# Peripherals.net
KiCad netlist of a schematic drawn in Altium Designer
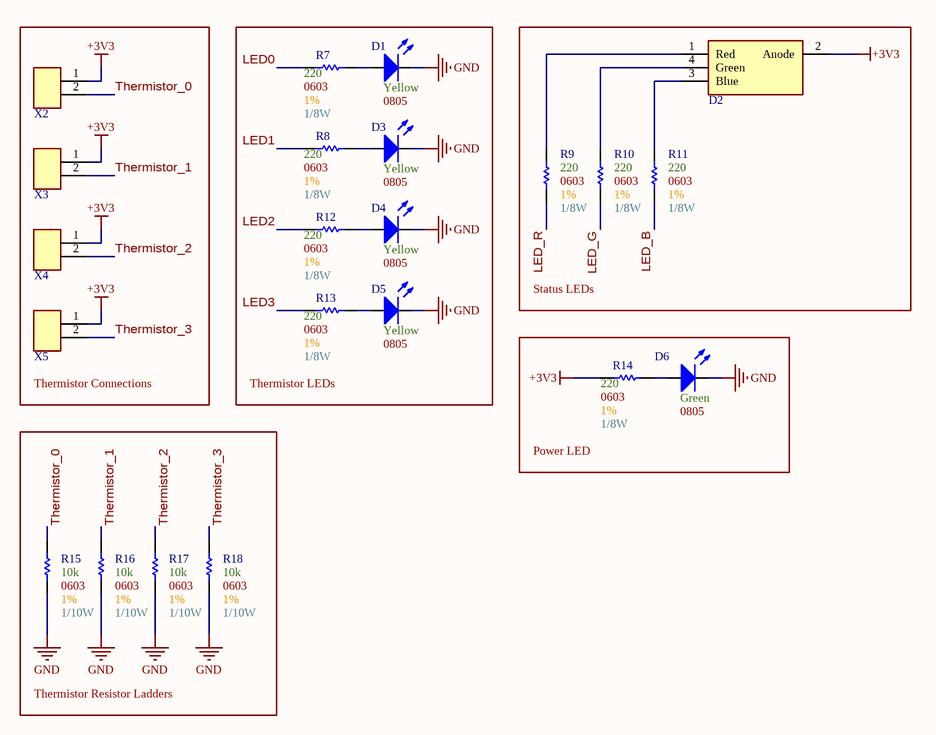
[diagram p0: Peripherals.SchDoc]

(export (version "E")
  (design (tool "Eeschema 10.0.6"))
  (components
    (comp (ref "D1")
      (value "[LED] SMD 0805 Yellow")
      (footprint "[LED] SMD 0805")
      (description "LY R976-PS-36-0-20-R18")
      (fields (field (name "COLOR") "Yellow") (field (name "SIZE PACKAGE") "0805"))
      (libsource (lib "LEDs") (part "[LED] SMD 0805 Yellow"))
    )
    (comp (ref "D2")
      (value "[LED] SMD RGB 1.55x1.55mm")
      (footprint "[LED] SMD RGB 1.55x1.55mm")
      (description "LTST-E143EGBW-P1")
      (libsource (lib "LEDs") (part "[LED] SMD RGB 1.55x1.55mm"))
    )
    (comp (ref "D3")
      (value "[LED] SMD 0805 Yellow")
      (footprint "[LED] SMD 0805")
      (description "LY R976-PS-36-0-20-R18")
      (fields (field (name "COLOR") "Yellow") (field (name "SIZE PACKAGE") "0805"))
      (libsource (lib "LEDs") (part "[LED] SMD 0805 Yellow"))
    )
    (comp (ref "D4")
      (value "[LED] SMD 0805 Yellow")
      (footprint "[LED] SMD 0805")
      (description "LY R976-PS-36-0-20-R18")
      (fields (field (name "COLOR") "Yellow") (field (name "SIZE PACKAGE") "0805"))
      (libsource (lib "LEDs") (part "[LED] SMD 0805 Yellow"))
    )
    (comp (ref "D5")
      (value "[LED] SMD 0805 Yellow")
      (footprint "[LED] SMD 0805")
      (description "LY R976-PS-36-0-20-R18")
      (fields (field (name "COLOR") "Yellow") (field (name "SIZE PACKAGE") "0805"))
      (libsource (lib "LEDs") (part "[LED] SMD 0805 Yellow"))
    )
    (comp (ref "D6")
      (value "[LED] SMD 0805 Green")
      (footprint "[LED] SMD 0805")
      (description "LG R971-KN-1-0-20-R18")
      (fields (field (name "COLOR") "Green") (field (name "SIZE PACKAGE") "0805"))
      (libsource (lib "LEDs") (part "[LED] SMD 0805 Green"))
    )
    (comp (ref "R7")
      (value "[220] SMD 0603 1% 1/10W")
      (footprint "[Res] SMD 0603")
      (description "CRGCQ0805F220R")
      (fields
        (field (name "WATTAGE") "1/8W")
        (field (name "TOLERANCE") "1%")
        (field (name "RESISTANCE") "220")
        (field (name "SIZE PACKAGE") "0603")
      )
      (libsource (lib "Resistors") (part "[220] SMD 0603 1% 1/10W"))
    )
    (comp (ref "R8")
      (value "[220] SMD 0603 1% 1/10W")
      (footprint "[Res] SMD 0603")
      (description "CRGCQ0805F220R")
      (fields
        (field (name "WATTAGE") "1/8W")
        (field (name "TOLERANCE") "1%")
        (field (name "RESISTANCE") "220")
        (field (name "SIZE PACKAGE") "0603")
      )
      (libsource (lib "Resistors") (part "[220] SMD 0603 1% 1/10W"))
    )
    (comp (ref "R9")
      (value "[220] SMD 0603 1% 1/10W")
      (footprint "[Res] SMD 0603")
      (description "CRGCQ0805F220R")
      (fields
        (field (name "WATTAGE") "1/8W")
        (field (name "TOLERANCE") "1%")
        (field (name "RESISTANCE") "220")
        (field (name "SIZE PACKAGE") "0603")
      )
      (libsource (lib "Resistors") (part "[220] SMD 0603 1% 1/10W"))
    )
    (comp (ref "R10")
      (value "[220] SMD 0603 1% 1/10W")
      (footprint "[Res] SMD 0603")
      (description "CRGCQ0805F220R")
      (fields
        (field (name "WATTAGE") "1/8W")
        (field (name "TOLERANCE") "1%")
        (field (name "RESISTANCE") "220")
        (field (name "SIZE PACKAGE") "0603")
      )
      (libsource (lib "Resistors") (part "[220] SMD 0603 1% 1/10W"))
    )
    (comp (ref "R11")
      (value "[220] SMD 0603 1% 1/10W")
      (footprint "[Res] SMD 0603")
      (description "CRGCQ0805F220R")
      (fields
        (field (name "WATTAGE") "1/8W")
        (field (name "TOLERANCE") "1%")
        (field (name "RESISTANCE") "220")
        (field (name "SIZE PACKAGE") "0603")
      )
      (libsource (lib "Resistors") (part "[220] SMD 0603 1% 1/10W"))
    )
    (comp (ref "R12")
      (value "[220] SMD 0603 1% 1/10W")
      (footprint "[Res] SMD 0603")
      (description "CRGCQ0805F220R")
      (fields
        (field (name "WATTAGE") "1/8W")
        (field (name "TOLERANCE") "1%")
        (field (name "RESISTANCE") "220")
        (field (name "SIZE PACKAGE") "0603")
      )
      (libsource (lib "Resistors") (part "[220] SMD 0603 1% 1/10W"))
    )
    (comp (ref "R13")
      (value "[220] SMD 0603 1% 1/10W")
      (footprint "[Res] SMD 0603")
      (description "CRGCQ0805F220R")
      (fields
        (field (name "WATTAGE") "1/8W")
        (field (name "TOLERANCE") "1%")
        (field (name "RESISTANCE") "220")
        (field (name "SIZE PACKAGE") "0603")
      )
      (libsource (lib "Resistors") (part "[220] SMD 0603 1% 1/10W"))
    )
    (comp (ref "R14")
      (value "[220] SMD 0603 1% 1/10W")
      (footprint "[Res] SMD 0603")
      (description "CRGCQ0805F220R")
      (fields
        (field (name "WATTAGE") "1/8W")
        (field (name "TOLERANCE") "1%")
        (field (name "RESISTANCE") "220")
        (field (name "SIZE PACKAGE") "0603")
      )
      (libsource (lib "Resistors") (part "[220] SMD 0603 1% 1/10W"))
    )
    (comp (ref "R15")
      (value "[10k] SMD 0603 1% 1/8W")
      (footprint "[Res] SMD 0603")
      (description "RMCF0603FT10K0")
      (fields
        (field (name "WATTAGE") "1/10W")
        (field (name "TOLERANCE") "1%")
        (field (name "RESISTANCE") "10k")
        (field (name "SIZE PACKAGE") "0603")
      )
      (libsource (lib "Resistors") (part "[10k] SMD 0603 1% 1/8W"))
    )
    (comp (ref "R16")
      (value "[10k] SMD 0603 1% 1/8W")
      (footprint "[Res] SMD 0603")
      (description "RMCF0603FT10K0")
      (fields
        (field (name "WATTAGE") "1/10W")
        (field (name "TOLERANCE") "1%")
        (field (name "RESISTANCE") "10k")
        (field (name "SIZE PACKAGE") "0603")
      )
      (libsource (lib "Resistors") (part "[10k] SMD 0603 1% 1/8W"))
    )
    (comp (ref "R17")
      (value "[10k] SMD 0603 1% 1/8W")
      (footprint "[Res] SMD 0603")
      (description "RMCF0603FT10K0")
      (fields
        (field (name "WATTAGE") "1/10W")
        (field (name "TOLERANCE") "1%")
        (field (name "RESISTANCE") "10k")
        (field (name "SIZE PACKAGE") "0603")
      )
      (libsource (lib "Resistors") (part "[10k] SMD 0603 1% 1/8W"))
    )
    (comp (ref "R18")
      (value "[10k] SMD 0603 1% 1/8W")
      (footprint "[Res] SMD 0603")
      (description "RMCF0603FT10K0")
      (fields
        (field (name "WATTAGE") "1/10W")
        (field (name "TOLERANCE") "1%")
        (field (name "RESISTANCE") "10k")
        (field (name "SIZE PACKAGE") "0603")
      )
      (libsource (lib "Resistors") (part "[10k] SMD 0603 1% 1/8W"))
    )
    (comp (ref "X2")
      (value "[Sherlock] 2pin")
      (footprint "[Sherlock] 2pin")
      (description "0353620250")
      (libsource (lib "Connectors") (part "[Sherlock] 2pin"))
    )
    (comp (ref "X3")
      (value "[Sherlock] 2pin")
      (footprint "[Sherlock] 2pin")
      (description "0353620250")
      (libsource (lib "Connectors") (part "[Sherlock] 2pin"))
    )
    (comp (ref "X4")
      (value "[Sherlock] 2pin")
      (footprint "[Sherlock] 2pin")
      (description "0353620250")
      (libsource (lib "Connectors") (part "[Sherlock] 2pin"))
    )
    (comp (ref "X5")
      (value "[Sherlock] 2pin")
      (footprint "[Sherlock] 2pin")
      (description "0353620250")
      (libsource (lib "Connectors") (part "[Sherlock] 2pin"))
    )
  )
  (nets
    (net (code "1") (name "+3V3") (class "Default")
      (node (ref "D2") (pin "2") (pinfunction "Anode_2") (pintype "passive"))
      (node (ref "R14") (pin "1") (pinfunction "1_1") (pintype "passive"))
      (node (ref "X2") (pin "1") (pintype "passive"))
      (node (ref "X3") (pin "1") (pintype "passive"))
      (node (ref "X4") (pin "1") (pintype "passive"))
      (node (ref "X5") (pin "1") (pintype "passive"))
    )
    (net (code "2") (name "/LED0") (class "Default")
      (node (ref "R7") (pin "1") (pinfunction "1_1") (pintype "passive"))
    )
    (net (code "3") (name "/LED1") (class "Default")
      (node (ref "R8") (pin "1") (pinfunction "1_1") (pintype "passive"))
    )
    (net (code "4") (name "/LED2") (class "Default")
      (node (ref "R12") (pin "1") (pinfunction "1_1") (pintype "passive"))
    )
    (net (code "5") (name "/LED3") (class "Default")
      (node (ref "R13") (pin "1") (pinfunction "1_1") (pintype "passive"))
    )
    (net (code "6") (name "/LED_B") (class "Default")
      (node (ref "R11") (pin "1") (pinfunction "1_1") (pintype "passive"))
    )
    (net (code "7") (name "/LED_G") (class "Default")
      (node (ref "R10") (pin "1") (pinfunction "1_1") (pintype "passive"))
    )
    (net (code "8") (name "/LED_R") (class "Default")
      (node (ref "R9") (pin "1") (pinfunction "1_1") (pintype "passive"))
    )
    (net (code "9") (name "/Thermistor_0") (class "Default")
      (node (ref "R15") (pin "2") (pinfunction "2_2") (pintype "passive"))
      (node (ref "X2") (pin "2") (pintype "passive"))
    )
    (net (code "10") (name "/Thermistor_1") (class "Default")
      (node (ref "R16") (pin "2") (pinfunction "2_2") (pintype "passive"))
      (node (ref "X3") (pin "2") (pintype "passive"))
    )
    (net (code "11") (name "/Thermistor_2") (class "Default")
      (node (ref "R17") (pin "2") (pinfunction "2_2") (pintype "passive"))
      (node (ref "X4") (pin "2") (pintype "passive"))
    )
    (net (code "12") (name "/Thermistor_3") (class "Default")
      (node (ref "R18") (pin "2") (pinfunction "2_2") (pintype "passive"))
      (node (ref "X5") (pin "2") (pintype "passive"))
    )
    (net (code "13") (name "GND") (class "Default")
      (node (ref "D1") (pin "2") (pinfunction "Cathode_2") (pintype "passive"))
      (node (ref "D3") (pin "2") (pinfunction "Cathode_2") (pintype "passive"))
      (node (ref "D4") (pin "2") (pinfunction "Cathode_2") (pintype "passive"))
      (node (ref "D5") (pin "2") (pinfunction "Cathode_2") (pintype "passive"))
      (node (ref "D6") (pin "2") (pinfunction "Cathode_2") (pintype "passive"))
      (node (ref "R15") (pin "1") (pinfunction "1_1") (pintype "passive"))
      (node (ref "R16") (pin "1") (pinfunction "1_1") (pintype "passive"))
      (node (ref "R17") (pin "1") (pinfunction "1_1") (pintype "passive"))
      (node (ref "R18") (pin "1") (pinfunction "1_1") (pintype "passive"))
    )
    (net (code "14") (name "Net-(D1-Anode)") (class "Default")
      (node (ref "D1") (pin "1") (pinfunction "Anode_1") (pintype "passive"))
      (node (ref "R7") (pin "2") (pinfunction "2_2") (pintype "passive"))
    )
    (net (code "15") (name "Net-(D2-Blue)") (class "Default")
      (node (ref "D2") (pin "3") (pinfunction "Blue_3") (pintype "passive"))
      (node (ref "R11") (pin "2") (pinfunction "2_2") (pintype "passive"))
    )
    (net (code "16") (name "Net-(D2-Green)") (class "Default")
      (node (ref "D2") (pin "4") (pinfunction "Green_4") (pintype "passive"))
      (node (ref "R10") (pin "2") (pinfunction "2_2") (pintype "passive"))
    )
    (net (code "17") (name "Net-(D2-Red)") (class "Default")
      (node (ref "D2") (pin "1") (pinfunction "Red_1") (pintype "passive"))
      (node (ref "R9") (pin "2") (pinfunction "2_2") (pintype "passive"))
    )
    (net (code "18") (name "Net-(D3-Anode)") (class "Default")
      (node (ref "D3") (pin "1") (pinfunction "Anode_1") (pintype "passive"))
      (node (ref "R8") (pin "2") (pinfunction "2_2") (pintype "passive"))
    )
    (net (code "19") (name "Net-(D4-Anode)") (class "Default")
      (node (ref "D4") (pin "1") (pinfunction "Anode_1") (pintype "passive"))
      (node (ref "R12") (pin "2") (pinfunction "2_2") (pintype "passive"))
    )
    (net (code "20") (name "Net-(D5-Anode)") (class "Default")
      (node (ref "D5") (pin "1") (pinfunction "Anode_1") (pintype "passive"))
      (node (ref "R13") (pin "2") (pinfunction "2_2") (pintype "passive"))
    )
    (net (code "21") (name "Net-(D6-Anode)") (class "Default")
      (node (ref "D6") (pin "1") (pinfunction "Anode_1") (pintype "passive"))
      (node (ref "R14") (pin "2") (pinfunction "2_2") (pintype "passive"))
    )
  )
)
